# SD_Smart_Card.net
KiCad netlist of a schematic drawn in Altium Designer
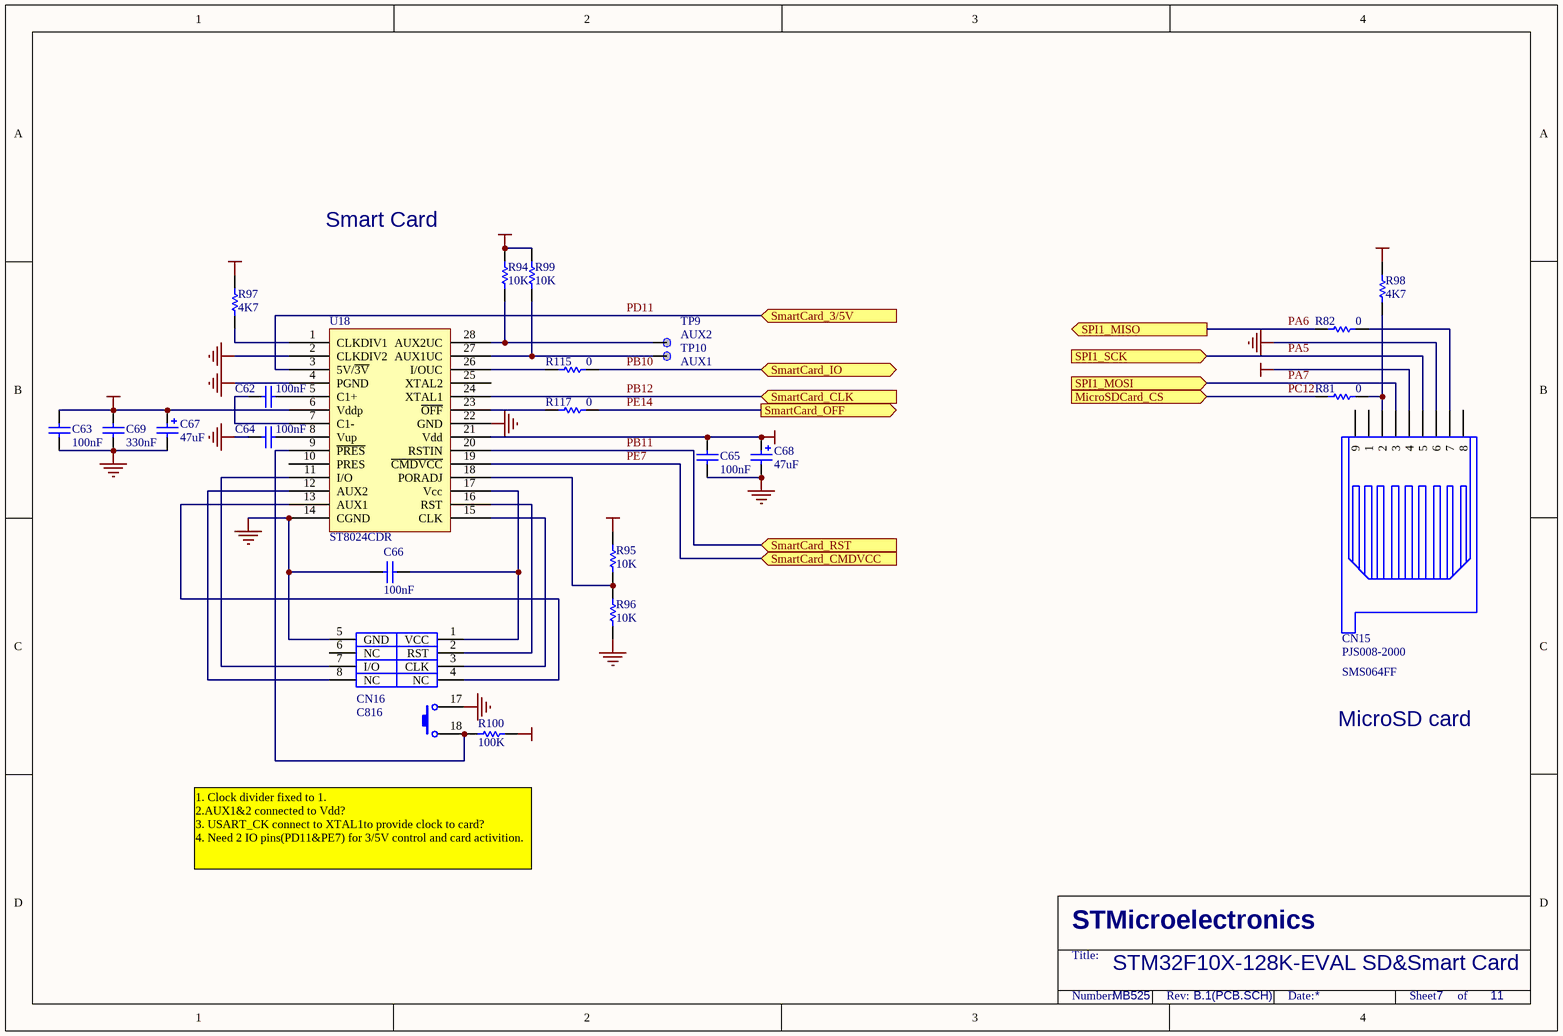
[diagram p0: SD&Smart Card.SchDoc]

(export (version "E")
  (design (tool "Eeschema 10.0.6"))
  (components
    (comp (ref "C62")
      (value "100nF")
      (footprint "0603P")
      (description "Capacitor")
      (fields (field (name "PUBLISHER") "Altium Limited"))
      (libsource (lib "Miscellaneous Devices") (part "CAP"))
    )
    (comp (ref "C63")
      (value "100nF")
      (footprint "0603P")
      (description "Capacitor")
      (fields (field (name "PUBLISHER") "Altium Limited"))
      (libsource (lib "Miscellaneous Devices") (part "CAP"))
    )
    (comp (ref "C64")
      (value "100nF")
      (footprint "0603P")
      (description "Capacitor")
      (fields (field (name "PUBLISHER") "Altium Limited"))
      (libsource (lib "Miscellaneous Devices") (part "CAP"))
    )
    (comp (ref "C65")
      (value "100nF")
      (footprint "0603P")
      (description "Capacitor")
      (fields (field (name "PUBLISHER") "Altium Limited"))
      (libsource (lib "Miscellaneous Devices") (part "CAP"))
    )
    (comp (ref "C66")
      (value "100nF")
      (footprint "0603P")
      (description "Capacitor")
      (fields (field (name "PUBLISHER") "Altium Limited"))
      (libsource (lib "Miscellaneous Devices") (part "CAP"))
    )
    (comp (ref "C67")
      (value "47uF")
      (footprint "TAN-B")
      (description "Polarized Capacitor (Radial)")
      (fields (field (name "PUBLISHER") "Altium Limited"))
      (libsource (lib "Miscellaneous Devices") (part "Cap Pol1"))
    )
    (comp (ref "C68")
      (value "47uF")
      (footprint "TAN-B")
      (description "Polarized Capacitor (Radial)")
      (fields (field (name "PUBLISHER") "Altium Limited"))
      (libsource (lib "Miscellaneous Devices") (part "Cap Pol1"))
    )
    (comp (ref "C69")
      (value "330nF")
      (description "Capacitor")
      (fields (field (name "PUBLISHER") "Altium Limited"))
      (libsource (lib "Miscellaneous Devices") (part "CAP"))
    )
    (comp (ref "CN15")
      (value "PJS008-2000")
      (footprint "MSD(PJS008)")
      (libsource (lib "MB525") (part "SMS016AFA5E"))
    )
    (comp (ref "CN16")
      (value "C816")
      (footprint "SAM(C816)")
      (libsource (lib "MB525") (part "Smart_card_CN"))
    )
    (comp (ref "R81")
      (value "0")
      (description "Resistor")
      (fields (field (name "PUBLISHER") "Altium Limited"))
      (libsource (lib "Miscellaneous Devices") (part "Res1"))
    )
    (comp (ref "R82")
      (value "0")
      (description "Resistor")
      (fields (field (name "PUBLISHER") "Altium Limited"))
      (libsource (lib "Miscellaneous Devices") (part "Res1"))
    )
    (comp (ref "R94")
      (value "10K")
      (description "Resistor")
      (fields (field (name "PUBLISHER") "Altium Limited"))
      (libsource (lib "Miscellaneous Devices") (part "Res1"))
    )
    (comp (ref "R95")
      (value "10K")
      (description "Resistor")
      (fields (field (name "PUBLISHER") "Altium Limited"))
      (libsource (lib "Miscellaneous Devices") (part "Res1"))
    )
    (comp (ref "R96")
      (value "10K")
      (description "Resistor")
      (fields (field (name "PUBLISHER") "Altium Limited"))
      (libsource (lib "Miscellaneous Devices") (part "Res1"))
    )
    (comp (ref "R97")
      (value "4K7")
      (description "Resistor")
      (fields (field (name "PUBLISHER") "Altium Limited"))
      (libsource (lib "Miscellaneous Devices") (part "Res1"))
    )
    (comp (ref "R98")
      (value "4K7")
      (description "Resistor")
      (fields (field (name "PUBLISHER") "Altium Limited"))
      (libsource (lib "Miscellaneous Devices") (part "Res1"))
    )
    (comp (ref "R99")
      (value "10K")
      (description "Resistor")
      (fields (field (name "PUBLISHER") "Altium Limited"))
      (libsource (lib "Miscellaneous Devices") (part "Res1"))
    )
    (comp (ref "R100")
      (value "100K")
      (description "Resistor")
      (fields (field (name "PUBLISHER") "Altium Limited"))
      (libsource (lib "Miscellaneous Devices") (part "Res1"))
    )
    (comp (ref "R115")
      (value "0")
      (description "Resistor")
      (fields (field (name "PUBLISHER") "Altium Limited"))
      (libsource (lib "Miscellaneous Devices") (part "Res1"))
    )
    (comp (ref "R117")
      (value "0")
      (description "Resistor")
      (fields (field (name "PUBLISHER") "Altium Limited"))
      (libsource (lib "Miscellaneous Devices") (part "Res1"))
    )
    (comp (ref "TP9") (value "AUX2") (footprint "TP") (libsource (lib "*") (part "TP")))
    (comp (ref "TP10") (value "AUX1") (footprint "TP") (libsource (lib "*") (part "TP")))
    (comp (ref "U18") (value "ST8024CDR") (footprint "SO28") (libsource (lib "MB525") (part "ST8024CTR")))
  )
  (nets
    (net (code "1") (name "+3V3") (class "Default")
      (node (ref "C65") (pin "1") (pinfunction "1_1") (pintype "passive"))
      (node (ref "C68") (pin "1") (pinfunction "1_1") (pintype "passive"))
      (node (ref "CN15") (pin "4") (pinfunction "4_4") (pintype "passive"))
      (node (ref "R100") (pin "1") (pinfunction "1_1") (pintype "passive"))
      (node (ref "R94") (pin "1") (pinfunction "1_1") (pintype "passive"))
      (node (ref "R95") (pin "1") (pinfunction "1_1") (pintype "passive"))
      (node (ref "R97") (pin "1") (pinfunction "1_1") (pintype "passive"))
      (node (ref "R98") (pin "2") (pinfunction "2_2") (pintype "passive"))
      (node (ref "R99") (pin "1") (pinfunction "1_1") (pintype "passive"))
      (node (ref "U18") (pin "21") (pinfunction "Vdd_21") (pintype "passive"))
    )
    (net (code "2") (name "+5V") (class "Default")
      (node (ref "C63") (pin "1") (pinfunction "1_1") (pintype "passive"))
      (node (ref "C67") (pin "1") (pinfunction "1_1") (pintype "passive"))
      (node (ref "C69") (pin "1") (pinfunction "1_1") (pintype "passive"))
      (node (ref "U18") (pin "6") (pinfunction "Vddp_6") (pintype "passive"))
    )
    (net (code "3") (name "/PA5") (class "Default")
      (node (ref "CN15") (pin "5") (pinfunction "5_5") (pintype "passive"))
    )
    (net (code "4") (name "/PA6") (class "Default")
      (node (ref "R82") (pin "1") (pinfunction "1_1") (pintype "passive"))
    )
    (net (code "5") (name "/PA7") (class "Default")
      (node (ref "CN15") (pin "3") (pinfunction "3_3") (pintype "passive"))
    )
    (net (code "6") (name "/PB10") (class "Default")
      (node (ref "R115") (pin "2") (pinfunction "2_2") (pintype "passive"))
    )
    (net (code "7") (name "/PB11") (class "Default")
      (node (ref "U18") (pin "20") (pinfunction "RSTIN_20") (pintype "passive"))
    )
    (net (code "8") (name "/PB12") (class "Default")
      (node (ref "U18") (pin "24") (pinfunction "XTAL1_24") (pintype "passive"))
    )
    (net (code "9") (name "/PC12") (class "Default")
      (node (ref "R81") (pin "2") (pinfunction "2_2") (pintype "passive"))
    )
    (net (code "10") (name "/PD11") (class "Default")
      (node (ref "U18") (pin "3") (pinfunction "5V/~{3V}_3") (pintype "passive"))
    )
    (net (code "11") (name "/PE7") (class "Default")
      (node (ref "U18") (pin "19") (pinfunction "~{CMDVCC}_19") (pintype "passive"))
    )
    (net (code "12") (name "/PE14") (class "Default")
      (node (ref "R117") (pin "1") (pinfunction "1_1") (pintype "passive"))
    )
    (net (code "13") (name "GND") (class "Default")
      (node (ref "C63") (pin "2") (pinfunction "2_2") (pintype "passive"))
      (node (ref "C64") (pin "2") (pinfunction "2_2") (pintype "passive"))
      (node (ref "C65") (pin "2") (pinfunction "2_2") (pintype "passive"))
      (node (ref "C66") (pin "1") (pinfunction "1_1") (pintype "passive"))
      (node (ref "C67") (pin "2") (pinfunction "2_2") (pintype "passive"))
      (node (ref "C68") (pin "2") (pinfunction "2_2") (pintype "passive"))
      (node (ref "C69") (pin "2") (pinfunction "2_2") (pintype "passive"))
      (node (ref "CN15") (pin "6") (pinfunction "6_6") (pintype "passive"))
      (node (ref "CN16") (pin "17") (pintype "passive"))
      (node (ref "CN16") (pin "5") (pinfunction "GND_5") (pintype "passive"))
      (node (ref "R96") (pin "2") (pinfunction "2_2") (pintype "passive"))
      (node (ref "U18") (pin "14") (pinfunction "CGND_14") (pintype "passive"))
      (node (ref "U18") (pin "2") (pinfunction "CLKDIV2_2") (pintype "passive"))
      (node (ref "U18") (pin "22") (pinfunction "GND_22") (pintype "passive"))
      (node (ref "U18") (pin "4") (pinfunction "PGND_4") (pintype "passive"))
    )
    (net (code "14") (name "Net-(CN15-Pad2)") (class "Default")
      (node (ref "CN15") (pin "2") (pinfunction "2_2") (pintype "passive"))
      (node (ref "R81") (pin "1") (pinfunction "1_1") (pintype "passive"))
      (node (ref "R98") (pin "1") (pinfunction "1_1") (pintype "passive"))
    )
    (net (code "15") (name "Net-(CN15-Pad7)") (class "Default")
      (node (ref "CN15") (pin "7") (pinfunction "7_7") (pintype "passive"))
      (node (ref "R82") (pin "2") (pinfunction "2_2") (pintype "passive"))
    )
    (net (code "16") (name "Net-(CN16-CLK)") (class "Default")
      (node (ref "CN16") (pin "3") (pinfunction "CLK_3") (pintype "passive"))
      (node (ref "U18") (pin "15") (pinfunction "CLK_15") (pintype "passive"))
    )
    (net (code "17") (name "Net-(CN16-I{slash}O)") (class "Default")
      (node (ref "CN16") (pin "7") (pinfunction "I/O_7") (pintype "passive"))
      (node (ref "U18") (pin "11") (pinfunction "I/O_11") (pintype "passive"))
    )
    (net (code "18") (name "Net-(CN16-RST)") (class "Default")
      (node (ref "CN16") (pin "2") (pinfunction "RST_2") (pintype "passive"))
      (node (ref "U18") (pin "16") (pinfunction "RST_16") (pintype "passive"))
    )
    (net (code "19") (name "Net-(CN16-VCC)") (class "Default")
      (node (ref "C66") (pin "2") (pinfunction "2_2") (pintype "passive"))
      (node (ref "CN16") (pin "1") (pinfunction "VCC_1") (pintype "passive"))
      (node (ref "U18") (pin "17") (pinfunction "Vcc_17") (pintype "passive"))
    )
    (net (code "20") (name "Net-(U18-AUX1)") (class "Default")
      (node (ref "CN16") (pin "4") (pinfunction "NC_4") (pintype "passive"))
      (node (ref "U18") (pin "13") (pinfunction "AUX1_13") (pintype "passive"))
    )
    (net (code "21") (name "Net-(U18-AUX1UC)") (class "Default")
      (node (ref "R99") (pin "2") (pinfunction "2_2") (pintype "passive"))
      (node (ref "TP10") (pin "1") (pinfunction "1_1") (pintype "passive"))
      (node (ref "U18") (pin "27") (pinfunction "AUX1UC_27") (pintype "passive"))
    )
    (net (code "22") (name "Net-(U18-AUX2)") (class "Default")
      (node (ref "CN16") (pin "8") (pinfunction "NC_8") (pintype "passive"))
      (node (ref "U18") (pin "12") (pinfunction "AUX2_12") (pintype "passive"))
    )
    (net (code "23") (name "Net-(U18-AUX2UC)") (class "Default")
      (node (ref "R94") (pin "2") (pinfunction "2_2") (pintype "passive"))
      (node (ref "TP9") (pin "1") (pinfunction "1_1") (pintype "passive"))
      (node (ref "U18") (pin "28") (pinfunction "AUX2UC_28") (pintype "passive"))
    )
    (net (code "24") (name "Net-(U18-C1+)") (class "Default")
      (node (ref "C62") (pin "2") (pinfunction "2_2") (pintype "passive"))
      (node (ref "U18") (pin "5") (pinfunction "C1+_5") (pintype "passive"))
    )
    (net (code "25") (name "Net-(U18-C1-)") (class "Default")
      (node (ref "C62") (pin "1") (pinfunction "1_1") (pintype "passive"))
      (node (ref "U18") (pin "7") (pinfunction "C1-_7") (pintype "passive"))
    )
    (net (code "26") (name "Net-(U18-CLKDIV1)") (class "Default")
      (node (ref "R97") (pin "2") (pinfunction "2_2") (pintype "passive"))
      (node (ref "U18") (pin "1") (pinfunction "CLKDIV1_1") (pintype "passive"))
    )
    (net (code "27") (name "Net-(U18-I{slash}OUC)") (class "Default")
      (node (ref "R115") (pin "1") (pinfunction "1_1") (pintype "passive"))
      (node (ref "U18") (pin "26") (pinfunction "I/OUC_26") (pintype "passive"))
    )
    (net (code "28") (name "Net-(U18-PORADJ)") (class "Default")
      (node (ref "R95") (pin "2") (pinfunction "2_2") (pintype "passive"))
      (node (ref "R96") (pin "1") (pinfunction "1_1") (pintype "passive"))
      (node (ref "U18") (pin "18") (pinfunction "PORADJ_18") (pintype "passive"))
    )
    (net (code "29") (name "Net-(U18-Vup)") (class "Default")
      (node (ref "C64") (pin "1") (pinfunction "1_1") (pintype "passive"))
      (node (ref "U18") (pin "8") (pinfunction "Vup_8") (pintype "passive"))
    )
    (net (code "30") (name "Net-(U18-~{OFF})") (class "Default")
      (node (ref "R117") (pin "2") (pinfunction "2_2") (pintype "passive"))
      (node (ref "U18") (pin "23") (pinfunction "~{OFF}_23") (pintype "passive"))
    )
    (net (code "31") (name "Net-(U18-~{PRES})") (class "Default")
      (node (ref "CN16") (pin "18") (pintype "passive"))
      (node (ref "R100") (pin "2") (pinfunction "2_2") (pintype "passive"))
      (node (ref "U18") (pin "9") (pinfunction "~{PRES}_9") (pintype "passive"))
    )
    (net (code "32") (name "unconnected-(CN15-Pad1)") (class "Default")
      (node (ref "CN15") (pin "1") (pinfunction "1_1") (pintype "passive"))
    )
    (net (code "33") (name "unconnected-(CN15-Pad8)") (class "Default")
      (node (ref "CN15") (pin "8") (pinfunction "8_8") (pintype "passive"))
    )
    (net (code "34") (name "unconnected-(CN15-Pad9)") (class "Default")
      (node (ref "CN15") (pin "9") (pinfunction "9_9") (pintype "passive"))
    )
    (net (code "35") (name "unconnected-(CN16-NC-Pad6)") (class "Default")
      (node (ref "CN16") (pin "6") (pinfunction "NC_6") (pintype "passive"))
    )
    (net (code "36") (name "unconnected-(U18-PRES-Pad10)") (class "Default")
      (node (ref "U18") (pin "10") (pinfunction "PRES_10") (pintype "passive"))
    )
    (net (code "37") (name "unconnected-(U18-XTAL2-Pad25)") (class "Default")
      (node (ref "U18") (pin "25") (pinfunction "XTAL2_25") (pintype "passive"))
    )
  )
)
